# ultrasonic.net
KiCad netlist of a schematic drawn in Altium Designer
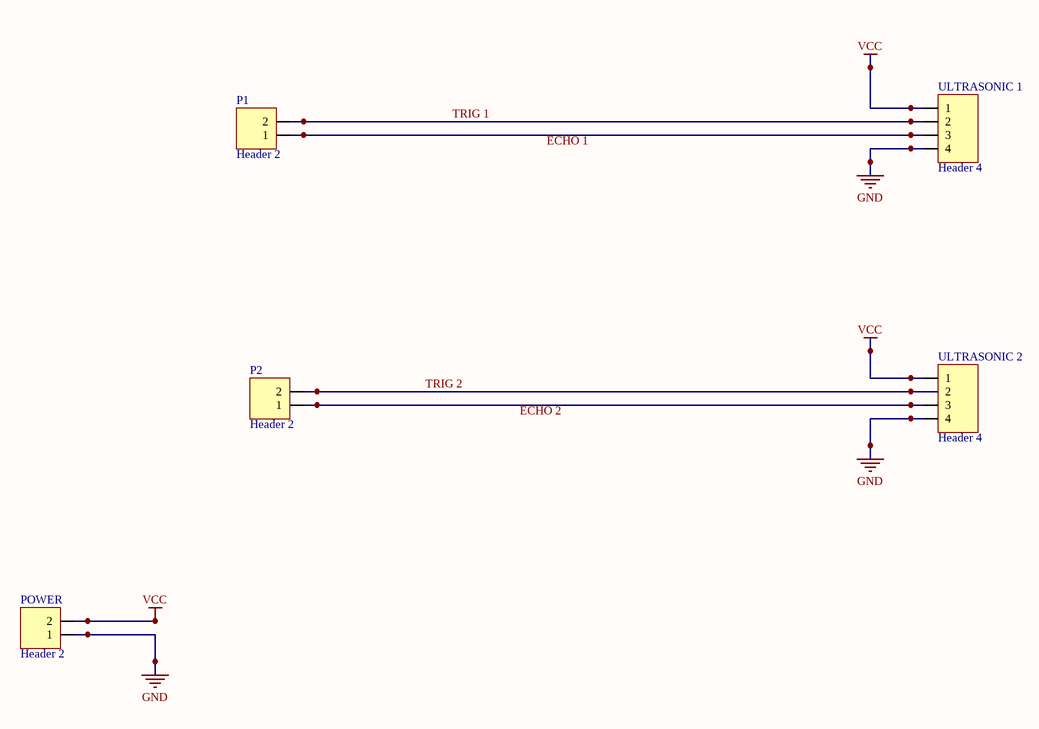
[diagram p0: ultrasonic.SchDoc]

(export (version "E")
  (design (tool "Eeschema 10.0.6"))
  (components
    (comp (ref "P1")
      (value "Header 2")
      (footprint "HDR1X2")
      (description "Header, 2-Pin")
      (fields (field (name "PUBLISHER") "Altium Limited"))
      (libsource (lib "Miscellaneous Connectors") (part "Header 2"))
    )
    (comp (ref "P2")
      (value "Header 2")
      (footprint "HDR1X2")
      (description "Header, 2-Pin")
      (fields (field (name "PUBLISHER") "Altium Limited"))
      (libsource (lib "Miscellaneous Connectors") (part "Header 2"))
    )
    (comp (ref "POWER")
      (value "Header 2")
      (footprint "HDR1X2")
      (description "Header, 2-Pin")
      (fields (field (name "PUBLISHER") "Altium Limited"))
      (libsource (lib "Miscellaneous Connectors") (part "Header 2"))
    )
    (comp (ref "ULTRASONIC 1")
      (value "Header 4")
      (footprint "HDR1X4")
      (description "Header, 4-Pin")
      (fields (field (name "PUBLISHER") "Altium Limited"))
      (libsource (lib "Miscellaneous Connectors") (part "Header 4"))
    )
    (comp (ref "ULTRASONIC 2")
      (value "Header 4")
      (footprint "HDR1X4")
      (description "Header, 4-Pin")
      (fields (field (name "PUBLISHER") "Altium Limited"))
      (libsource (lib "Miscellaneous Connectors") (part "Header 4"))
    )
  )
  (nets
    (net (code "3") (name "/TRIG 1") (class "Default")
      (node (ref "P1") (pin "2") (pinfunction "2_2") (pintype "passive"))
      (node (ref "ULTRASONIC 1") (pin "2") (pinfunction "2_2") (pintype "passive"))
    )
    (net (code "4") (name "/TRIG 2") (class "Default")
      (node (ref "P2") (pin "2") (pinfunction "2_2") (pintype "passive"))
      (node (ref "ULTRASONIC 2") (pin "2") (pinfunction "2_2") (pintype "passive"))
    )
    (net (code "5") (name "GND") (class "Default")
      (node (ref "POWER") (pin "1") (pinfunction "1_1") (pintype "passive"))
      (node (ref "ULTRASONIC 1") (pin "4") (pinfunction "4_4") (pintype "passive"))
      (node (ref "ULTRASONIC 2") (pin "4") (pinfunction "4_4") (pintype "passive"))
    )
    (net (code "6") (name "Net-(P1-Pad1)") (class "Default")
      (node (ref "P1") (pin "1") (pinfunction "1_1") (pintype "passive"))
      (node (ref "ULTRASONIC 1") (pin "3") (pinfunction "3_3") (pintype "passive"))
    )
    (net (code "7") (name "Net-(P2-Pad1)") (class "Default")
      (node (ref "P2") (pin "1") (pinfunction "1_1") (pintype "passive"))
      (node (ref "ULTRASONIC 2") (pin "3") (pinfunction "3_3") (pintype "passive"))
    )
    (net (code "8") (name "VCC") (class "Default")
      (node (ref "POWER") (pin "2") (pinfunction "2_2") (pintype "passive"))
      (node (ref "ULTRASONIC 1") (pin "1") (pinfunction "1_1") (pintype "passive"))
      (node (ref "ULTRASONIC 2") (pin "1") (pinfunction "1_1") (pintype "passive"))
    )
  )
)
